# Pneumatics_Board.net
KiCad netlist of a schematic drawn in Altium Designer
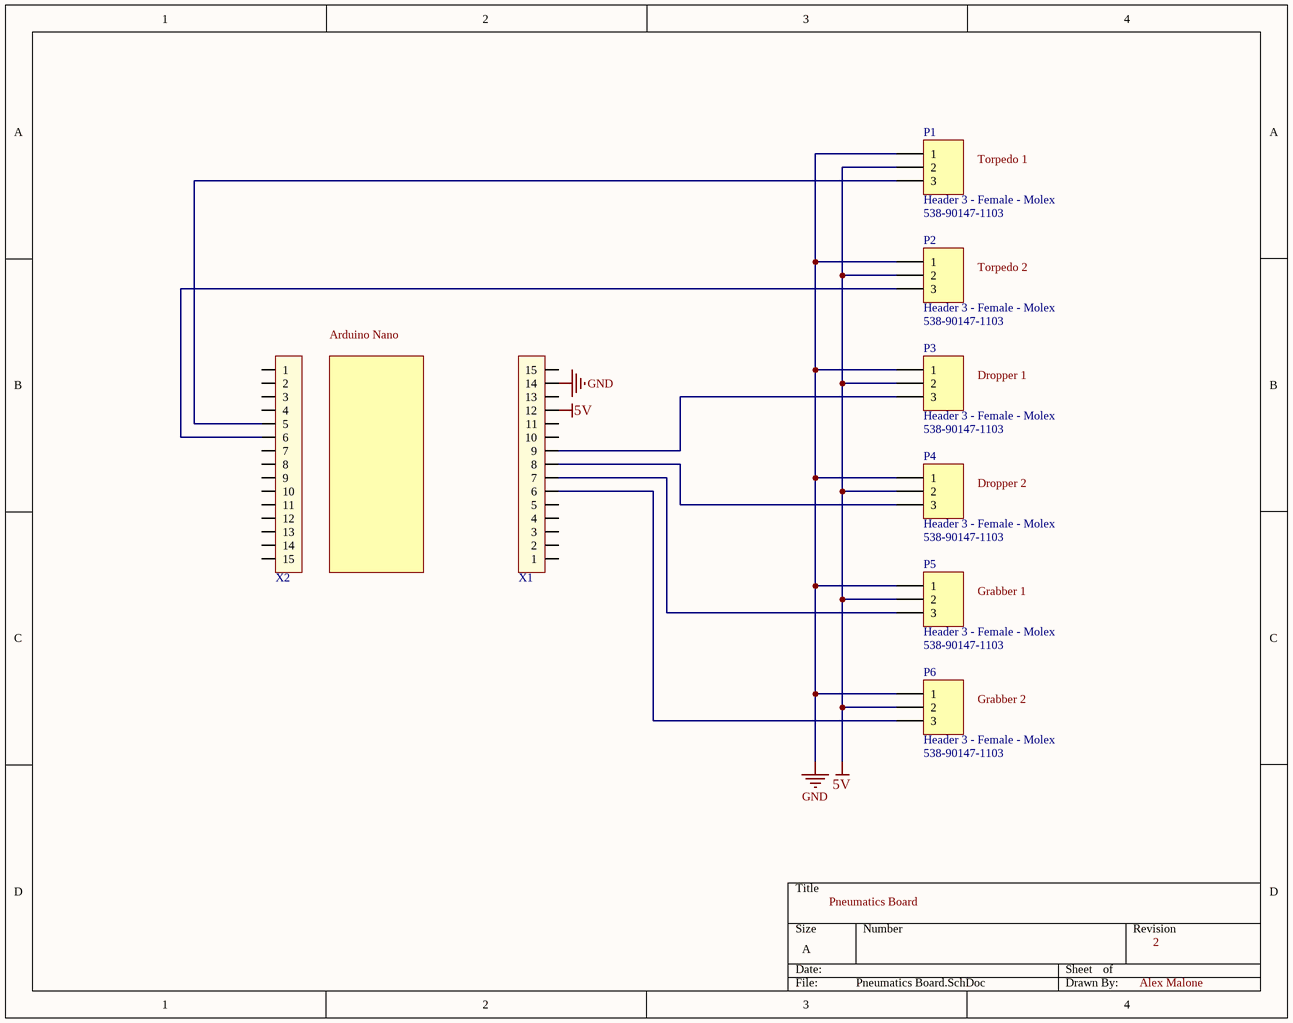
[diagram p0: Pneumatics Board.SchDoc]

(export (version "E")
  (design (tool "Eeschema 10.0.6"))
  (components
    (comp (ref "P1")
      (value "Header 3 - Female - Molex")
      (footprint "HDR1X3 - Female - Molex")
      (description "Header, 3-Pin")
      (fields
        (field (name "MANUFACTURER") "Molex")
        (field (name "MANUFACTURER PART NUMBER") "90147-1103")
        (field (name "SUPPLIER PART NUMBER 1") "538-90147-1103")
      )
      (libsource (lib "URC_Lib") (part "Header 3 - Female - Molex"))
    )
    (comp (ref "P2")
      (value "Header 3 - Female - Molex")
      (footprint "HDR1X3 - Female - Molex")
      (description "Header, 3-Pin")
      (fields
        (field (name "MANUFACTURER") "Molex")
        (field (name "MANUFACTURER PART NUMBER") "90147-1103")
        (field (name "SUPPLIER PART NUMBER 1") "538-90147-1103")
      )
      (libsource (lib "URC_Lib") (part "Header 3 - Female - Molex"))
    )
    (comp (ref "P3")
      (value "Header 3 - Female - Molex")
      (footprint "HDR1X3 - Female - Molex")
      (description "Header, 3-Pin")
      (fields
        (field (name "MANUFACTURER") "Molex")
        (field (name "MANUFACTURER PART NUMBER") "90147-1103")
        (field (name "SUPPLIER PART NUMBER 1") "538-90147-1103")
      )
      (libsource (lib "URC_Lib") (part "Header 3 - Female - Molex"))
    )
    (comp (ref "P4")
      (value "Header 3 - Female - Molex")
      (footprint "HDR1X3 - Female - Molex")
      (description "Header, 3-Pin")
      (fields
        (field (name "MANUFACTURER") "Molex")
        (field (name "MANUFACTURER PART NUMBER") "90147-1103")
        (field (name "SUPPLIER PART NUMBER 1") "538-90147-1103")
      )
      (libsource (lib "URC_Lib") (part "Header 3 - Female - Molex"))
    )
    (comp (ref "P5")
      (value "Header 3 - Female - Molex")
      (footprint "HDR1X3 - Female - Molex")
      (description "Header, 3-Pin")
      (fields
        (field (name "MANUFACTURER") "Molex")
        (field (name "MANUFACTURER PART NUMBER") "90147-1103")
        (field (name "SUPPLIER PART NUMBER 1") "538-90147-1103")
      )
      (libsource (lib "URC_Lib") (part "Header 3 - Female - Molex"))
    )
    (comp (ref "P6")
      (value "Header 3 - Female - Molex")
      (footprint "HDR1X3 - Female - Molex")
      (description "Header, 3-Pin")
      (fields
        (field (name "MANUFACTURER") "Molex")
        (field (name "MANUFACTURER PART NUMBER") "90147-1103")
        (field (name "SUPPLIER PART NUMBER 1") "538-90147-1103")
      )
      (libsource (lib "URC_Lib") (part "Header 3 - Female - Molex"))
    )
    (comp (ref "X1")
      (value "Header")
      (footprint "1x15 Header")
      (description "1x3 Header")
      (libsource (lib "URC") (part "1x15"))
    )
    (comp (ref "X2")
      (value "Header")
      (footprint "1x15 Header")
      (description "1x3 Header")
      (libsource (lib "") (part "1x15_1"))
    )
  )
  (nets
    (net (code "11") (name "5V") (class "Default")
      (node (ref "P1") (pin "2") (pinfunction "2_2") (pintype "passive"))
      (node (ref "P2") (pin "2") (pinfunction "2_2") (pintype "passive"))
      (node (ref "P3") (pin "2") (pinfunction "2_2") (pintype "passive"))
      (node (ref "P4") (pin "2") (pinfunction "2_2") (pintype "passive"))
      (node (ref "P5") (pin "2") (pinfunction "2_2") (pintype "passive"))
      (node (ref "P6") (pin "2") (pinfunction "2_2") (pintype "passive"))
      (node (ref "X1") (pin "12") (pinfunction "12_12") (pintype "passive"))
    )
    (net (code "12") (name "GND") (class "Default")
      (node (ref "P1") (pin "1") (pinfunction "1_1") (pintype "passive"))
      (node (ref "P2") (pin "1") (pinfunction "1_1") (pintype "passive"))
      (node (ref "P3") (pin "1") (pinfunction "1_1") (pintype "passive"))
      (node (ref "P4") (pin "1") (pinfunction "1_1") (pintype "passive"))
      (node (ref "P5") (pin "1") (pinfunction "1_1") (pintype "passive"))
      (node (ref "P6") (pin "1") (pinfunction "1_1") (pintype "passive"))
      (node (ref "X1") (pin "14") (pinfunction "14_14") (pintype "passive"))
    )
    (net (code "13") (name "Net-(P1-Pad3)") (class "Default")
      (node (ref "P1") (pin "3") (pinfunction "3_3") (pintype "passive"))
      (node (ref "X2") (pin "5") (pinfunction "5_5") (pintype "passive"))
    )
    (net (code "14") (name "Net-(P2-Pad3)") (class "Default")
      (node (ref "P2") (pin "3") (pinfunction "3_3") (pintype "passive"))
      (node (ref "X2") (pin "6") (pinfunction "6_6") (pintype "passive"))
    )
    (net (code "15") (name "Net-(P3-Pad3)") (class "Default")
      (node (ref "P3") (pin "3") (pinfunction "3_3") (pintype "passive"))
      (node (ref "X1") (pin "9") (pinfunction "9_9") (pintype "passive"))
    )
    (net (code "16") (name "Net-(P4-Pad3)") (class "Default")
      (node (ref "P4") (pin "3") (pinfunction "3_3") (pintype "passive"))
      (node (ref "X1") (pin "8") (pinfunction "8_8") (pintype "passive"))
    )
    (net (code "17") (name "Net-(P5-Pad3)") (class "Default")
      (node (ref "P5") (pin "3") (pinfunction "3_3") (pintype "passive"))
      (node (ref "X1") (pin "7") (pinfunction "7_7") (pintype "passive"))
    )
    (net (code "18") (name "Net-(P6-Pad3)") (class "Default")
      (node (ref "P6") (pin "3") (pinfunction "3_3") (pintype "passive"))
      (node (ref "X1") (pin "6") (pinfunction "6_6") (pintype "passive"))
    )
    (net (code "19") (name "unconnected-(X1-Pad1)") (class "Default")
      (node (ref "X1") (pin "1") (pinfunction "1_1") (pintype "passive"))
    )
    (net (code "20") (name "unconnected-(X1-Pad2)") (class "Default")
      (node (ref "X1") (pin "2") (pinfunction "2_2") (pintype "passive"))
    )
    (net (code "21") (name "unconnected-(X1-Pad3)") (class "Default")
      (node (ref "X1") (pin "3") (pinfunction "3_3") (pintype "passive"))
    )
    (net (code "22") (name "unconnected-(X1-Pad4)") (class "Default")
      (node (ref "X1") (pin "4") (pinfunction "4_4") (pintype "passive"))
    )
    (net (code "23") (name "unconnected-(X1-Pad5)") (class "Default")
      (node (ref "X1") (pin "5") (pinfunction "5_5") (pintype "passive"))
    )
    (net (code "24") (name "unconnected-(X1-Pad10)") (class "Default")
      (node (ref "X1") (pin "10") (pinfunction "10_10") (pintype "passive"))
    )
    (net (code "25") (name "unconnected-(X1-Pad11)") (class "Default")
      (node (ref "X1") (pin "11") (pinfunction "11_11") (pintype "passive"))
    )
    (net (code "26") (name "unconnected-(X1-Pad13)") (class "Default")
      (node (ref "X1") (pin "13") (pinfunction "13_13") (pintype "passive"))
    )
    (net (code "27") (name "unconnected-(X1-Pad15)") (class "Default")
      (node (ref "X1") (pin "15") (pinfunction "15_15") (pintype "passive"))
    )
    (net (code "28") (name "unconnected-(X2-Pad1)") (class "Default")
      (node (ref "X2") (pin "1") (pinfunction "1_1") (pintype "passive"))
    )
    (net (code "29") (name "unconnected-(X2-Pad2)") (class "Default")
      (node (ref "X2") (pin "2") (pinfunction "2_2") (pintype "passive"))
    )
    (net (code "30") (name "unconnected-(X2-Pad3)") (class "Default")
      (node (ref "X2") (pin "3") (pinfunction "3_3") (pintype "passive"))
    )
    (net (code "31") (name "unconnected-(X2-Pad4)") (class "Default")
      (node (ref "X2") (pin "4") (pinfunction "4_4") (pintype "passive"))
    )
    (net (code "32") (name "unconnected-(X2-Pad7)") (class "Default")
      (node (ref "X2") (pin "7") (pinfunction "7_7") (pintype "passive"))
    )
    (net (code "33") (name "unconnected-(X2-Pad8)") (class "Default")
      (node (ref "X2") (pin "8") (pinfunction "8_8") (pintype "passive"))
    )
    (net (code "34") (name "unconnected-(X2-Pad9)") (class "Default")
      (node (ref "X2") (pin "9") (pinfunction "9_9") (pintype "passive"))
    )
    (net (code "35") (name "unconnected-(X2-Pad10)") (class "Default")
      (node (ref "X2") (pin "10") (pinfunction "10_10") (pintype "passive"))
    )
    (net (code "36") (name "unconnected-(X2-Pad11)") (class "Default")
      (node (ref "X2") (pin "11") (pinfunction "11_11") (pintype "passive"))
    )
    (net (code "37") (name "unconnected-(X2-Pad12)") (class "Default")
      (node (ref "X2") (pin "12") (pinfunction "12_12") (pintype "passive"))
    )
    (net (code "38") (name "unconnected-(X2-Pad13)") (class "Default")
      (node (ref "X2") (pin "13") (pinfunction "13_13") (pintype "passive"))
    )
    (net (code "39") (name "unconnected-(X2-Pad14)") (class "Default")
      (node (ref "X2") (pin "14") (pinfunction "14_14") (pintype "passive"))
    )
    (net (code "40") (name "unconnected-(X2-Pad15)") (class "Default")
      (node (ref "X2") (pin "15") (pinfunction "15_15") (pintype "passive"))
    )
  )
)
